# fillcap_bp.net
KiCad netlist of a schematic drawn in Altium Designer
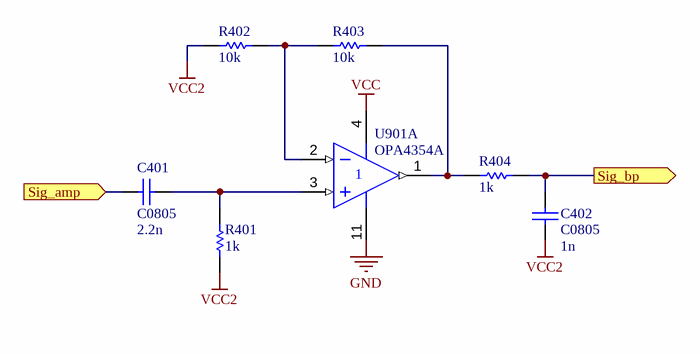
[diagram p0: fillcap_bp.SchDoc]

(export (version "E")
  (design (tool "Eeschema 10.0.6"))
  (components
    (comp (ref "C401")
      (value "C0805")
      (footprint "0805")
      (description "Ceramic Chip Capacitor - Standard")
      (fields (field (name "ALTIUM_VALUE") "2.2n") (field (name "PUBLISHER") "Altium Limited"))
      (libsource (lib "KEMET Chip Capacitor") (part "C0805"))
    )
    (comp (ref "C402")
      (value "C0805")
      (footprint "0805")
      (description "Ceramic Chip Capacitor - Standard")
      (fields (field (name "ALTIUM_VALUE") "1n") (field (name "PUBLISHER") "Altium Limited"))
      (libsource (lib "KEMET Chip Capacitor") (part "C0805"))
    )
    (comp (ref "R401")
      (value "1k")
      (footprint "ERA-0805")
      (fields (field (name "PUBLISHER") "Altium Limited"))
      (libsource (lib "Panasonic Resistor") (part "ERAS"))
    )
    (comp (ref "R402")
      (value "10k")
      (footprint "ERA-0805")
      (fields (field (name "PUBLISHER") "Altium Limited"))
      (libsource (lib "Panasonic Resistor") (part "ERAS"))
    )
    (comp (ref "R403")
      (value "10k")
      (footprint "ERA-0805")
      (fields (field (name "PUBLISHER") "Altium Limited"))
      (libsource (lib "Panasonic Resistor") (part "ERAS"))
    )
    (comp (ref "R404")
      (value "1k")
      (footprint "ERA-0805")
      (fields (field (name "PUBLISHER") "Altium Limited"))
      (libsource (lib "Panasonic Resistor") (part "ERAS"))
    )
    (comp (ref "U901")
      (value "OPA4354A")
      (footprint "D014_N")
      (description "Quadruple Operational Amplifier")
      (fields (field (name "PUBLISHER") "Altium Limited"))
      (libsource (lib "TI Operational Amplifier") (part "LM324AD"))
    )
  )
  (nets
    (net (code "1") (name "/Sig_amp") (class "Default")
      (node (ref "C401") (pin "2") (pinfunction "2_2") (pintype "passive"))
    )
    (net (code "2") (name "/Sig_bp") (class "Default")
      (node (ref "C402") (pin "1") (pinfunction "1_1") (pintype "passive"))
      (node (ref "R404") (pin "2") (pinfunction "2_2") (pintype "passive"))
    )
    (net (code "3") (name "GND") (class "Default")
      (node (ref "U901") (pin "11") (pinfunction "V-_11") (pintype "power_in"))
    )
    (net (code "4") (name "Net-(U901A-IN+)") (class "Default")
      (node (ref "C401") (pin "1") (pinfunction "1_1") (pintype "passive"))
      (node (ref "R401") (pin "1") (pinfunction "1_1") (pintype "passive"))
      (node (ref "U901") (pin "3") (pinfunction "IN+_3") (pintype "input"))
    )
    (net (code "5") (name "Net-(U901A-IN-)") (class "Default")
      (node (ref "R402") (pin "2") (pinfunction "2_2") (pintype "passive"))
      (node (ref "R403") (pin "1") (pinfunction "1_1") (pintype "passive"))
      (node (ref "U901") (pin "2") (pinfunction "IN-_2") (pintype "input"))
    )
    (net (code "6") (name "Net-(U901A-OUT)") (class "Default")
      (node (ref "R403") (pin "2") (pinfunction "2_2") (pintype "passive"))
      (node (ref "R404") (pin "1") (pinfunction "1_1") (pintype "passive"))
      (node (ref "U901") (pin "1") (pinfunction "OUT_1") (pintype "output"))
    )
    (net (code "7") (name "VCC") (class "Default")
      (node (ref "U901") (pin "4") (pinfunction "V+_4") (pintype "power_in"))
    )
    (net (code "8") (name "VCC2") (class "Default")
      (node (ref "C402") (pin "2") (pinfunction "2_2") (pintype "passive"))
      (node (ref "R401") (pin "2") (pinfunction "2_2") (pintype "passive"))
      (node (ref "R402") (pin "1") (pinfunction "1_1") (pintype "passive"))
    )
  )
)
